# MCU.net
KiCad netlist of a schematic drawn in Altium Designer
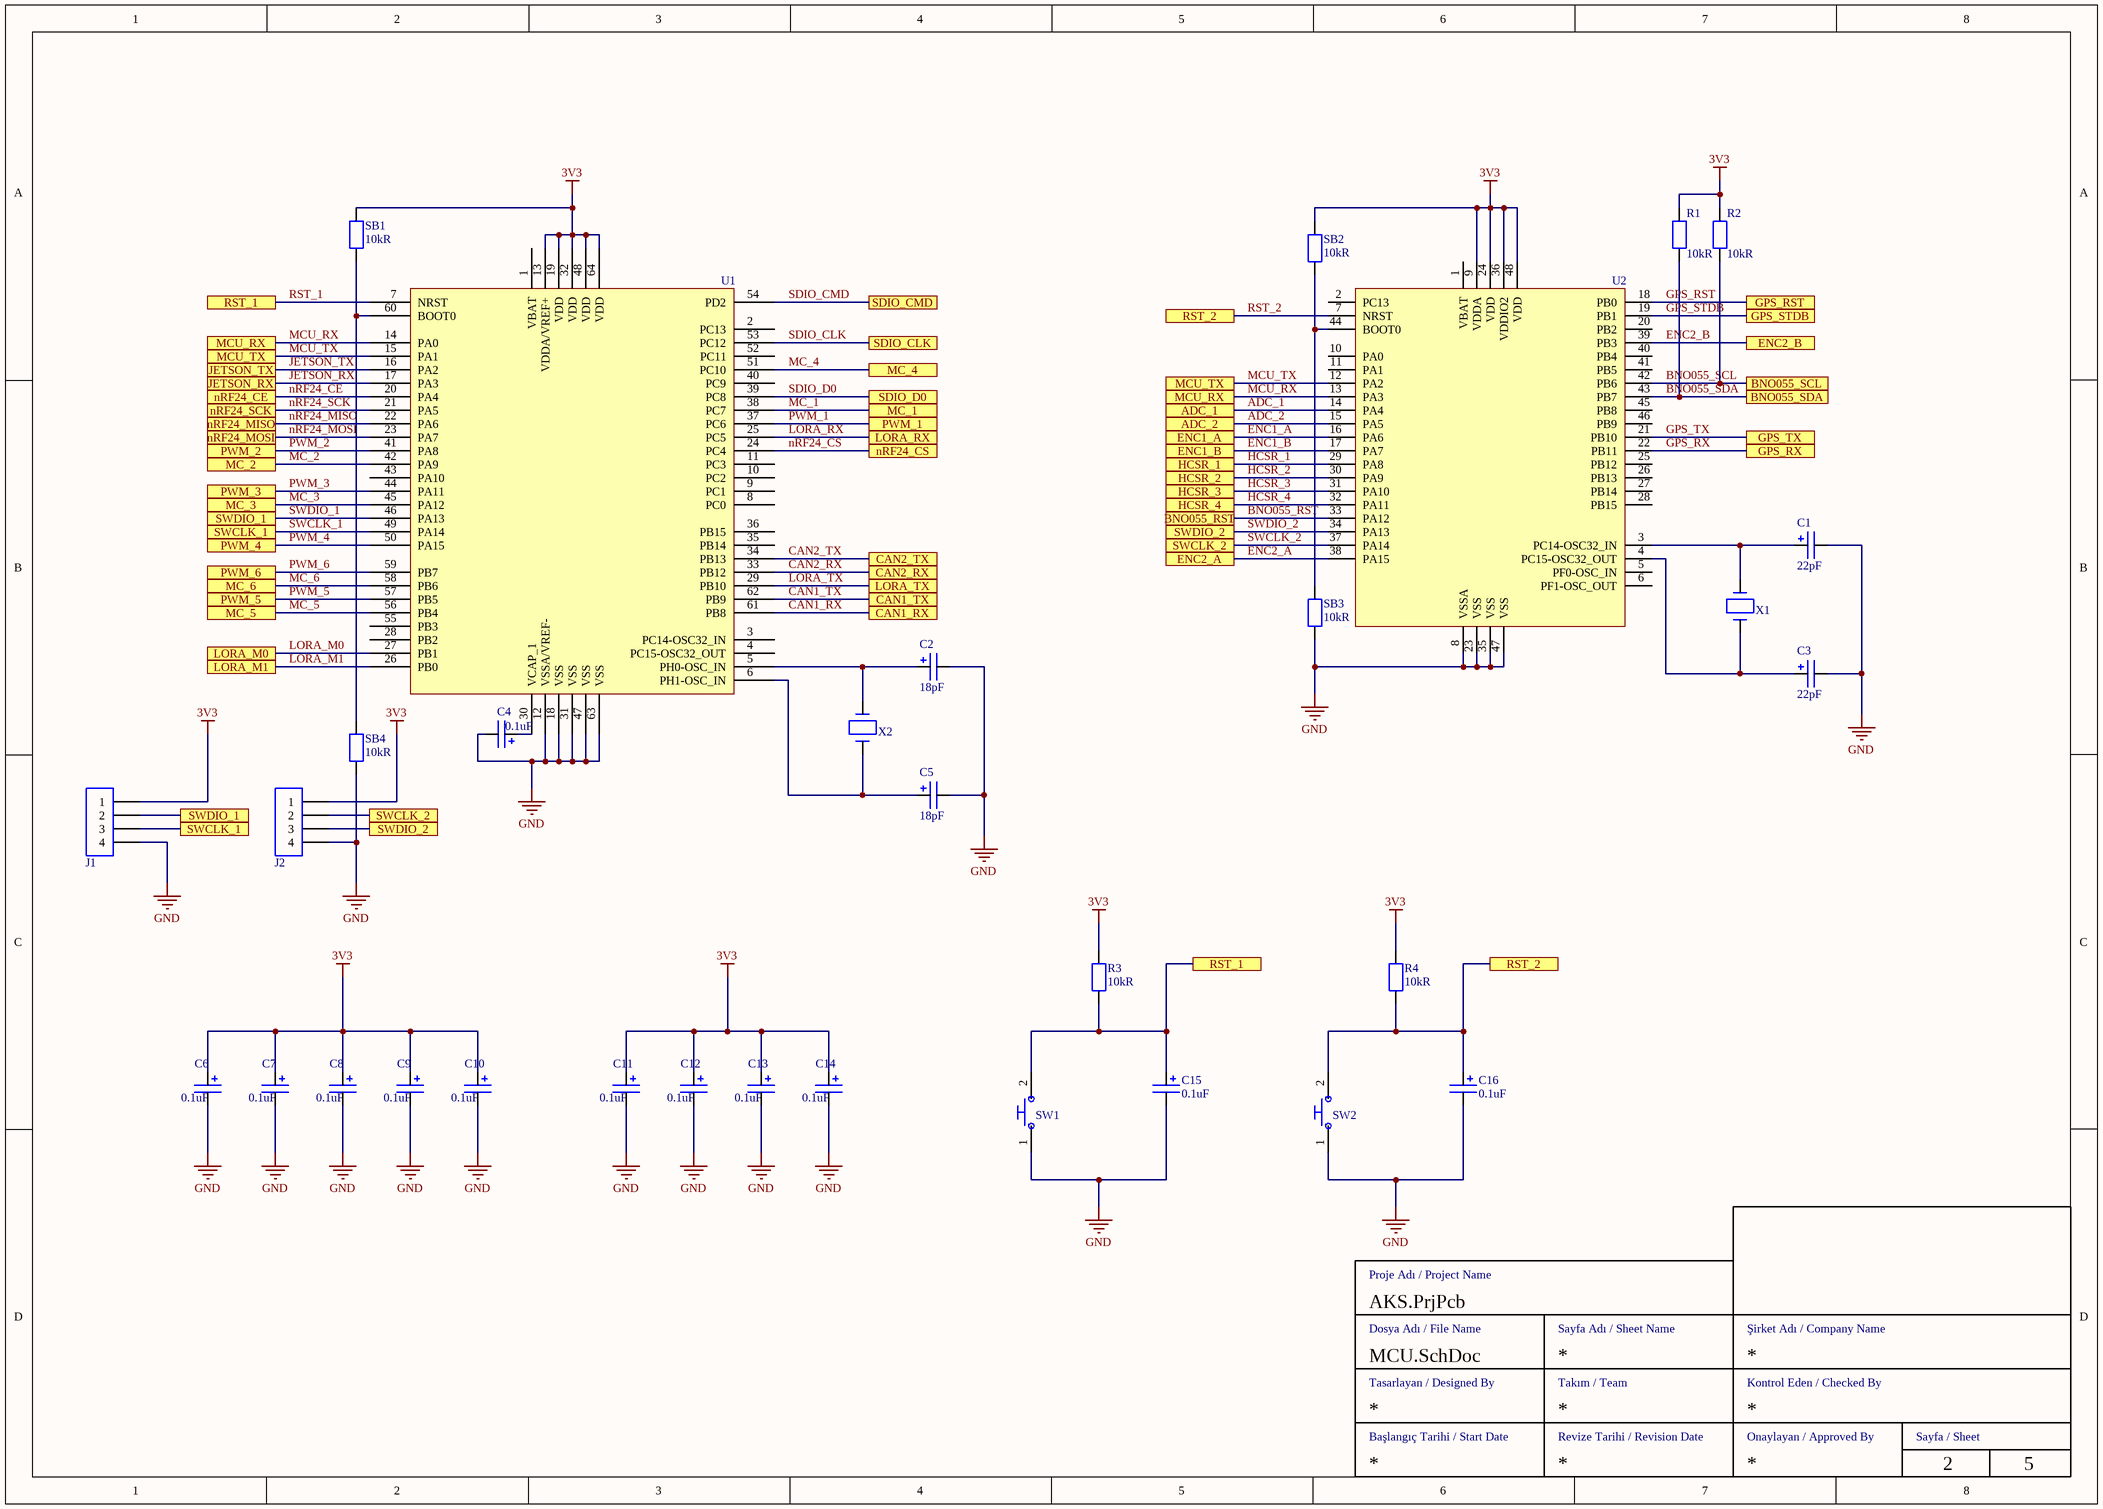
[diagram p0: MCU.SchDoc]

(export (version "E")
  (design (tool "Eeschema 10.0.6"))
  (components
    (comp (ref "C1")
      (value "22pF")
      (footprint "CAP 0603")
      (description "Multilayer Ceramic Capacitor")
      (fields (field (name "Comment") "CAP 0603"))
      (libsource (lib "Kaptanyums Lib") (part "CAP 0603"))
    )
    (comp (ref "C2")
      (value "18pF")
      (footprint "CAP 0603")
      (description "Multilayer Ceramic Capacitor")
      (fields (field (name "Comment") "CAP 0603"))
      (libsource (lib "Kaptanyums Lib") (part "CAP 0603"))
    )
    (comp (ref "C3")
      (value "22pF")
      (footprint "CAP 0603")
      (description "Multilayer Ceramic Capacitor")
      (fields (field (name "Comment") "CAP 0603"))
      (libsource (lib "Kaptanyums Lib") (part "CAP 0603"))
    )
    (comp (ref "C4")
      (value "0.1uF")
      (footprint "CAP 0603")
      (description "Multilayer Ceramic Capacitor")
      (fields (field (name "Comment") "CAP 0603"))
      (libsource (lib "Kaptanyums Lib") (part "CAP 0603"))
    )
    (comp (ref "C5")
      (value "18pF")
      (footprint "CAP 0603")
      (description "Multilayer Ceramic Capacitor")
      (fields (field (name "Comment") "CAP 0603"))
      (libsource (lib "Kaptanyums Lib") (part "CAP 0603"))
    )
    (comp (ref "C6")
      (value "0.1uF")
      (footprint "CAP 0603")
      (description "Multilayer Ceramic Capacitor")
      (fields (field (name "Comment") "CAP 0603"))
      (libsource (lib "Kaptanyums Lib") (part "CAP 0603"))
    )
    (comp (ref "C7")
      (value "0.1uF")
      (footprint "CAP 0603")
      (description "Multilayer Ceramic Capacitor")
      (fields (field (name "Comment") "CAP 0603"))
      (libsource (lib "Kaptanyums Lib") (part "CAP 0603"))
    )
    (comp (ref "C8")
      (value "0.1uF")
      (footprint "CAP 0603")
      (description "Multilayer Ceramic Capacitor")
      (fields (field (name "Comment") "CAP 0603"))
      (libsource (lib "Kaptanyums Lib") (part "CAP 0603"))
    )
    (comp (ref "C9")
      (value "0.1uF")
      (footprint "CAP 0603")
      (description "Multilayer Ceramic Capacitor")
      (fields (field (name "Comment") "CAP 0603"))
      (libsource (lib "Kaptanyums Lib") (part "CAP 0603"))
    )
    (comp (ref "C10")
      (value "0.1uF")
      (footprint "CAP 0603")
      (description "Multilayer Ceramic Capacitor")
      (fields (field (name "Comment") "CAP 0603"))
      (libsource (lib "Kaptanyums Lib") (part "CAP 0603"))
    )
    (comp (ref "C11")
      (value "0.1uF")
      (footprint "CAP 0603")
      (description "Multilayer Ceramic Capacitor")
      (fields (field (name "Comment") "CAP 0603"))
      (libsource (lib "Kaptanyums Lib") (part "CAP 0603"))
    )
    (comp (ref "C12")
      (value "0.1uF")
      (footprint "CAP 0603")
      (description "Multilayer Ceramic Capacitor")
      (fields (field (name "Comment") "CAP 0603"))
      (libsource (lib "Kaptanyums Lib") (part "CAP 0603"))
    )
    (comp (ref "C13")
      (value "0.1uF")
      (footprint "CAP 0603")
      (description "Multilayer Ceramic Capacitor")
      (fields (field (name "Comment") "CAP 0603"))
      (libsource (lib "Kaptanyums Lib") (part "CAP 0603"))
    )
    (comp (ref "C14")
      (value "0.1uF")
      (footprint "CAP 0603")
      (description "Multilayer Ceramic Capacitor")
      (fields (field (name "Comment") "CAP 0603"))
      (libsource (lib "Kaptanyums Lib") (part "CAP 0603"))
    )
    (comp (ref "C15")
      (value "0.1uF")
      (footprint "CAP 0603")
      (description "Multilayer Ceramic Capacitor")
      (fields (field (name "Comment") "CAP 0603"))
      (libsource (lib "Kaptanyums Lib") (part "CAP 0603"))
    )
    (comp (ref "C16")
      (value "0.1uF")
      (footprint "CAP 0603")
      (description "Multilayer Ceramic Capacitor")
      (fields (field (name "Comment") "CAP 0603"))
      (libsource (lib "Kaptanyums Lib") (part "CAP 0603"))
    )
    (comp (ref "J1")
      (value "146285-4")
      (footprint "HMATHT00C41")
      (description "Header for PCB")
      (libsource (lib "Kaptanyums Lib") (part "HMATHT00C41"))
    )
    (comp (ref "J2")
      (value "146285-4")
      (footprint "HMATHT00C41")
      (description "Header for PCB")
      (libsource (lib "Kaptanyums Lib") (part "HMATHT00C41"))
    )
    (comp (ref "R1")
      (value "10kR")
      (footprint "RESISTOR 0603")
      (description "SMD Chip Resistor")
      (fields (field (name "Comment") "RES 0603"))
      (libsource (lib "Kaptanyums Lib") (part "RES 0603"))
    )
    (comp (ref "R2")
      (value "10kR")
      (footprint "RESISTOR 0603")
      (description "SMD Chip Resistor")
      (fields (field (name "Comment") "RES 0603"))
      (libsource (lib "Kaptanyums Lib") (part "RES 0603"))
    )
    (comp (ref "R3")
      (value "10kR")
      (footprint "RESISTOR 0603")
      (description "SMD Chip Resistor")
      (fields (field (name "Comment") "RES 0603"))
      (libsource (lib "Kaptanyums Lib") (part "RES 0603"))
    )
    (comp (ref "R4")
      (value "10kR")
      (footprint "RESISTOR 0603")
      (description "SMD Chip Resistor")
      (fields (field (name "Comment") "RES 0603"))
      (libsource (lib "Kaptanyums Lib") (part "RES 0603"))
    )
    (comp (ref "SB1")
      (value "10kR")
      (footprint "RESISTOR 0603")
      (description "SMD Chip Resistor")
      (fields (field (name "Comment") "RES 0603"))
      (libsource (lib "Kaptanyums Lib") (part "RES 0603"))
    )
    (comp (ref "SB2")
      (value "10kR")
      (footprint "RESISTOR 0603")
      (description "SMD Chip Resistor")
      (fields (field (name "Comment") "RES 0603"))
      (libsource (lib "Kaptanyums Lib") (part "RES 0603"))
    )
    (comp (ref "SB3")
      (value "10kR")
      (footprint "RESISTOR 0603")
      (description "SMD Chip Resistor")
      (fields (field (name "Comment") "RES 0603"))
      (libsource (lib "Kaptanyums Lib") (part "RES 0603"))
    )
    (comp (ref "SB4")
      (value "10kR")
      (footprint "RESISTOR 0603")
      (description "SMD Chip Resistor")
      (fields (field (name "Comment") "RES 0603"))
      (libsource (lib "Kaptanyums Lib") (part "RES 0603"))
    )
    (comp (ref "SW1")
      (value "DS1042-03")
      (footprint "SWITCH-6X6")
      (description "Switch")
      (libsource (lib "Kaptanyums Lib") (part "DS1042-03"))
    )
    (comp (ref "SW2")
      (value "DS1042-03")
      (footprint "SWITCH-6X6")
      (description "Switch")
      (libsource (lib "Kaptanyums Lib") (part "DS1042-03"))
    )
    (comp (ref "U1")
      (value "STM32F446xC")
      (footprint "LQFP64")
      (description "STM32 ARM Cortex M4")
      (libsource (lib "Kaptanyums Lib") (part "STM32F446xC"))
    )
    (comp (ref "U2")
      (value "STM32F072C8")
      (footprint "LQFP48")
      (description "STM32 ARM Cortex M0")
      (libsource (lib "Kaptanyums Lib") (part "STM32F072C8"))
    )
    (comp (ref "X1")
      (value "RSM200S-32.768")
      (footprint "4-SOJ")
      (description "CRYSTAL")
      (libsource (lib "Kaptanyums Lib") (part "RSM200S-32.768"))
    )
    (comp (ref "X2")
      (value "ABM3-8.000")
      (footprint "2-SMD")
      (description "CRYSTAL")
      (libsource (lib "Kaptanyums Lib") (part "ABM3-8.000"))
    )
  )
  (nets
    (net (code "1") (name "/ADC_1") (class "Default")
      (node (ref "U2") (pin "14") (pinfunction "PA4_14") (pintype "passive"))
    )
    (net (code "2") (name "/ADC_2") (class "Default")
      (node (ref "U2") (pin "15") (pinfunction "PA5_15") (pintype "passive"))
    )
    (net (code "3") (name "/BNO055_RST") (class "Default")
      (node (ref "U2") (pin "33") (pinfunction "PA12_33") (pintype "passive"))
    )
    (net (code "4") (name "/BNO055_SCL") (class "Default")
      (node (ref "R2") (pin "1") (pinfunction "1_1") (pintype "passive"))
      (node (ref "U2") (pin "42") (pinfunction "PB6_42") (pintype "passive"))
    )
    (net (code "5") (name "/BNO055_SDA") (class "Default")
      (node (ref "R1") (pin "1") (pinfunction "1_1") (pintype "passive"))
      (node (ref "U2") (pin "43") (pinfunction "PB7_43") (pintype "passive"))
    )
    (net (code "6") (name "/CAN1_RX") (class "Default")
      (node (ref "U1") (pin "61") (pinfunction "PB8_61") (pintype "passive"))
    )
    (net (code "7") (name "/CAN1_TX") (class "Default")
      (node (ref "U1") (pin "62") (pinfunction "PB9_62") (pintype "passive"))
    )
    (net (code "8") (name "/CAN2_RX") (class "Default")
      (node (ref "U1") (pin "33") (pinfunction "PB12_33") (pintype "passive"))
    )
    (net (code "9") (name "/CAN2_TX") (class "Default")
      (node (ref "U1") (pin "34") (pinfunction "PB13_34") (pintype "passive"))
    )
    (net (code "10") (name "/ENC1_A") (class "Default")
      (node (ref "U2") (pin "16") (pinfunction "PA6_16") (pintype "passive"))
    )
    (net (code "11") (name "/ENC1_B") (class "Default")
      (node (ref "U2") (pin "17") (pinfunction "PA7_17") (pintype "passive"))
    )
    (net (code "12") (name "/ENC2_A") (class "Default")
      (node (ref "U2") (pin "38") (pinfunction "PA15_38") (pintype "passive"))
    )
    (net (code "13") (name "/ENC2_B") (class "Default")
      (node (ref "U2") (pin "39") (pinfunction "PB3_39") (pintype "passive"))
    )
    (net (code "14") (name "/GPS_RST") (class "Default")
      (node (ref "U2") (pin "18") (pinfunction "PB0_18") (pintype "passive"))
    )
    (net (code "15") (name "/GPS_RX") (class "Default")
      (node (ref "U2") (pin "22") (pinfunction "PB11_22") (pintype "passive"))
    )
    (net (code "16") (name "/GPS_STDB") (class "Default")
      (node (ref "U2") (pin "19") (pinfunction "PB1_19") (pintype "passive"))
    )
    (net (code "17") (name "/GPS_TX") (class "Default")
      (node (ref "U2") (pin "21") (pinfunction "PB10_21") (pintype "passive"))
    )
    (net (code "18") (name "/HCSR_1") (class "Default")
      (node (ref "U2") (pin "29") (pinfunction "PA8_29") (pintype "passive"))
    )
    (net (code "19") (name "/HCSR_2") (class "Default")
      (node (ref "U2") (pin "30") (pinfunction "PA9_30") (pintype "passive"))
    )
    (net (code "20") (name "/HCSR_3") (class "Default")
      (node (ref "U2") (pin "31") (pinfunction "PA10_31") (pintype "passive"))
    )
    (net (code "21") (name "/HCSR_4") (class "Default")
      (node (ref "U2") (pin "32") (pinfunction "PA11_32") (pintype "passive"))
    )
    (net (code "22") (name "/JETSON_RX") (class "Default")
      (node (ref "U1") (pin "17") (pinfunction "PA3_17") (pintype "passive"))
    )
    (net (code "23") (name "/JETSON_TX") (class "Default")
      (node (ref "U1") (pin "16") (pinfunction "PA2_16") (pintype "passive"))
    )
    (net (code "24") (name "/LORA_M0") (class "Default")
      (node (ref "U1") (pin "27") (pinfunction "PB1_27") (pintype "passive"))
    )
    (net (code "25") (name "/LORA_M1") (class "Default")
      (node (ref "U1") (pin "26") (pinfunction "PB0_26") (pintype "passive"))
    )
    (net (code "26") (name "/LORA_RX") (class "Default")
      (node (ref "U1") (pin "25") (pinfunction "PC5_25") (pintype "passive"))
    )
    (net (code "27") (name "/LORA_TX") (class "Default")
      (node (ref "U1") (pin "29") (pinfunction "PB10_29") (pintype "passive"))
    )
    (net (code "28") (name "/MCU_RX") (class "Default")
      (node (ref "U1") (pin "14") (pinfunction "PA0_14") (pintype "passive"))
      (node (ref "U2") (pin "13") (pinfunction "PA3_13") (pintype "passive"))
    )
    (net (code "29") (name "/MCU_TX") (class "Default")
      (node (ref "U1") (pin "15") (pinfunction "PA1_15") (pintype "passive"))
      (node (ref "U2") (pin "12") (pinfunction "PA2_12") (pintype "passive"))
    )
    (net (code "30") (name "/MC_1") (class "Default")
      (node (ref "U1") (pin "38") (pinfunction "PC7_38") (pintype "passive"))
    )
    (net (code "31") (name "/MC_2") (class "Default")
      (node (ref "U1") (pin "42") (pinfunction "PA9_42") (pintype "passive"))
    )
    (net (code "32") (name "/MC_3") (class "Default")
      (node (ref "U1") (pin "45") (pinfunction "PA12_45") (pintype "passive"))
    )
    (net (code "33") (name "/MC_4") (class "Default")
      (node (ref "U1") (pin "51") (pinfunction "PC10_51") (pintype "passive"))
    )
    (net (code "34") (name "/MC_5") (class "Default")
      (node (ref "U1") (pin "56") (pinfunction "PB4_56") (pintype "passive"))
    )
    (net (code "35") (name "/MC_6") (class "Default")
      (node (ref "U1") (pin "58") (pinfunction "PB6_58") (pintype "passive"))
    )
    (net (code "36") (name "/PWM_1") (class "Default")
      (node (ref "U1") (pin "37") (pinfunction "PC6_37") (pintype "passive"))
    )
    (net (code "37") (name "/PWM_2") (class "Default")
      (node (ref "U1") (pin "41") (pinfunction "PA8_41") (pintype "passive"))
    )
    (net (code "38") (name "/PWM_3") (class "Default")
      (node (ref "U1") (pin "44") (pinfunction "PA11_44") (pintype "passive"))
    )
    (net (code "39") (name "/PWM_4") (class "Default")
      (node (ref "U1") (pin "50") (pinfunction "PA15_50") (pintype "passive"))
    )
    (net (code "40") (name "/PWM_5") (class "Default")
      (node (ref "U1") (pin "57") (pinfunction "PB5_57") (pintype "passive"))
    )
    (net (code "41") (name "/PWM_6") (class "Default")
      (node (ref "U1") (pin "59") (pinfunction "PB7_59") (pintype "passive"))
    )
    (net (code "42") (name "/RST_1") (class "Default")
      (node (ref "C15") (pin "1") (pinfunction "1_1") (pintype "passive"))
      (node (ref "R3") (pin "1") (pinfunction "1_1") (pintype "passive"))
      (node (ref "SW1") (pin "2") (pinfunction "2_2") (pintype "passive"))
      (node (ref "U1") (pin "7") (pinfunction "NRST_7") (pintype "passive"))
    )
    (net (code "43") (name "/RST_2") (class "Default")
      (node (ref "C16") (pin "1") (pinfunction "1_1") (pintype "passive"))
      (node (ref "R4") (pin "1") (pinfunction "1_1") (pintype "passive"))
      (node (ref "SW2") (pin "2") (pinfunction "2_2") (pintype "passive"))
      (node (ref "U2") (pin "7") (pinfunction "NRST_7") (pintype "passive"))
    )
    (net (code "44") (name "/SDIO_CLK") (class "Default")
      (node (ref "U1") (pin "53") (pinfunction "PC12_53") (pintype "passive"))
    )
    (net (code "45") (name "/SDIO_CMD") (class "Default")
      (node (ref "U1") (pin "54") (pinfunction "PD2_54") (pintype "passive"))
    )
    (net (code "46") (name "/SDIO_D0") (class "Default")
      (node (ref "U1") (pin "39") (pinfunction "PC8_39") (pintype "passive"))
    )
    (net (code "47") (name "/SWCLK_1") (class "Default")
      (node (ref "J1") (pin "3") (pinfunction "3_3") (pintype "passive"))
      (node (ref "U1") (pin "49") (pinfunction "PA14_49") (pintype "passive"))
    )
    (net (code "48") (name "/SWCLK_2") (class "Default")
      (node (ref "J2") (pin "2") (pinfunction "2_2") (pintype "passive"))
      (node (ref "U2") (pin "37") (pinfunction "PA14_37") (pintype "passive"))
    )
    (net (code "49") (name "/SWDIO_1") (class "Default")
      (node (ref "J1") (pin "2") (pinfunction "2_2") (pintype "passive"))
      (node (ref "U1") (pin "46") (pinfunction "PA13_46") (pintype "passive"))
    )
    (net (code "50") (name "/SWDIO_2") (class "Default")
      (node (ref "J2") (pin "3") (pinfunction "3_3") (pintype "passive"))
      (node (ref "U2") (pin "34") (pinfunction "PA13_34") (pintype "passive"))
    )
    (net (code "51") (name "/nRF24_CE") (class "Default")
      (node (ref "U1") (pin "20") (pinfunction "PA4_20") (pintype "passive"))
    )
    (net (code "52") (name "/nRF24_CS") (class "Default")
      (node (ref "U1") (pin "24") (pinfunction "PC4_24") (pintype "passive"))
    )
    (net (code "53") (name "/nRF24_MISO") (class "Default")
      (node (ref "U1") (pin "22") (pinfunction "PA6_22") (pintype "passive"))
    )
    (net (code "54") (name "/nRF24_MOSI") (class "Default")
      (node (ref "U1") (pin "23") (pinfunction "PA7_23") (pintype "passive"))
    )
    (net (code "55") (name "/nRF24_SCK") (class "Default")
      (node (ref "U1") (pin "21") (pinfunction "PA5_21") (pintype "passive"))
    )
    (net (code "56") (name "3V3") (class "Default")
      (node (ref "C10") (pin "1") (pinfunction "1_1") (pintype "passive"))
      (node (ref "C11") (pin "1") (pinfunction "1_1") (pintype "passive"))
      (node (ref "C12") (pin "1") (pinfunction "1_1") (pintype "passive"))
      (node (ref "C13") (pin "1") (pinfunction "1_1") (pintype "passive"))
      (node (ref "C14") (pin "1") (pinfunction "1_1") (pintype "passive"))
      (node (ref "C6") (pin "1") (pinfunction "1_1") (pintype "passive"))
      (node (ref "C7") (pin "1") (pinfunction "1_1") (pintype "passive"))
      (node (ref "C8") (pin "1") (pinfunction "1_1") (pintype "passive"))
      (node (ref "C9") (pin "1") (pinfunction "1_1") (pintype "passive"))
      (node (ref "J1") (pin "1") (pinfunction "1_1") (pintype "passive"))
      (node (ref "J2") (pin "1") (pinfunction "1_1") (pintype "passive"))
      (node (ref "R1") (pin "2") (pinfunction "2_2") (pintype "passive"))
      (node (ref "R2") (pin "2") (pinfunction "2_2") (pintype "passive"))
      (node (ref "R3") (pin "2") (pinfunction "2_2") (pintype "passive"))
      (node (ref "R4") (pin "2") (pinfunction "2_2") (pintype "passive"))
      (node (ref "SB1") (pin "2") (pinfunction "2_2") (pintype "passive"))
      (node (ref "SB2") (pin "2") (pinfunction "2_2") (pintype "passive"))
      (node (ref "U1") (pin "13") (pinfunction "VDDA/VREF+_13") (pintype "passive"))
      (node (ref "U1") (pin "19") (pinfunction "VDD_19") (pintype "passive"))
      (node (ref "U1") (pin "32") (pinfunction "VDD_32") (pintype "passive"))
      (node (ref "U1") (pin "48") (pinfunction "VDD_48") (pintype "passive"))
      (node (ref "U1") (pin "64") (pinfunction "VDD_64") (pintype "passive"))
      (node (ref "U2") (pin "24") (pinfunction "VDD_24") (pintype "passive"))
      (node (ref "U2") (pin "36") (pinfunction "VDDIO2_36") (pintype "passive"))
      (node (ref "U2") (pin "48") (pinfunction "VDD_48") (pintype "passive"))
      (node (ref "U2") (pin "9") (pinfunction "VDDA_9") (pintype "passive"))
    )
    (net (code "57") (name "GND") (class "Default")
      (node (ref "C1") (pin "2") (pinfunction "2_2") (pintype "passive"))
      (node (ref "C10") (pin "2") (pinfunction "2_2") (pintype "passive"))
      (node (ref "C11") (pin "2") (pinfunction "2_2") (pintype "passive"))
      (node (ref "C12") (pin "2") (pinfunction "2_2") (pintype "passive"))
      (node (ref "C13") (pin "2") (pinfunction "2_2") (pintype "passive"))
      (node (ref "C14") (pin "2") (pinfunction "2_2") (pintype "passive"))
      (node (ref "C15") (pin "2") (pinfunction "2_2") (pintype "passive"))
      (node (ref "C16") (pin "2") (pinfunction "2_2") (pintype "passive"))
      (node (ref "C2") (pin "2") (pinfunction "2_2") (pintype "passive"))
      (node (ref "C3") (pin "2") (pinfunction "2_2") (pintype "passive"))
      (node (ref "C4") (pin "2") (pinfunction "2_2") (pintype "passive"))
      (node (ref "C5") (pin "2") (pinfunction "2_2") (pintype "passive"))
      (node (ref "C6") (pin "2") (pinfunction "2_2") (pintype "passive"))
      (node (ref "C7") (pin "2") (pinfunction "2_2") (pintype "passive"))
      (node (ref "C8") (pin "2") (pinfunction "2_2") (pintype "passive"))
      (node (ref "C9") (pin "2") (pinfunction "2_2") (pintype "passive"))
      (node (ref "J1") (pin "4") (pinfunction "4_4") (pintype "passive"))
      (node (ref "J2") (pin "4") (pinfunction "4_4") (pintype "passive"))
      (node (ref "SB3") (pin "1") (pinfunction "1_1") (pintype "passive"))
      (node (ref "SB4") (pin "1") (pinfunction "1_1") (pintype "passive"))
      (node (ref "SW1") (pin "1") (pinfunction "1_1") (pintype "passive"))
      (node (ref "SW2") (pin "1") (pinfunction "1_1") (pintype "passive"))
      (node (ref "U1") (pin "12") (pinfunction "VSSA/VREF-_12") (pintype "passive"))
      (node (ref "U1") (pin "18") (pinfunction "VSS_18") (pintype "passive"))
      (node (ref "U1") (pin "31") (pinfunction "VSS_31") (pintype "passive"))
      (node (ref "U1") (pin "47") (pinfunction "VSS_47") (pintype "passive"))
      (node (ref "U1") (pin "63") (pinfunction "VSS_63") (pintype "passive"))
      (node (ref "U2") (pin "23") (pinfunction "VSS_23") (pintype "passive"))
      (node (ref "U2") (pin "35") (pinfunction "VSS_35") (pintype "passive"))
      (node (ref "U2") (pin "47") (pinfunction "VSS_47") (pintype "passive"))
      (node (ref "U2") (pin "8") (pinfunction "VSSA_8") (pintype "passive"))
    )
    (net (code "58") (name "Net-(U1-BOOT0)") (class "Default")
      (node (ref "SB1") (pin "1") (pinfunction "1_1") (pintype "passive"))
      (node (ref "SB4") (pin "2") (pinfunction "2_2") (pintype "passive"))
      (node (ref "U1") (pin "60") (pinfunction "BOOT0_60") (pintype "passive"))
    )
    (net (code "59") (name "Net-(U1-PH0-OSC_IN)") (class "Default")
      (node (ref "C2") (pin "1") (pinfunction "1_1") (pintype "passive"))
      (node (ref "U1") (pin "5") (pinfunction "PH0-OSC_IN_5") (pintype "passive"))
      (node (ref "X2") (pin "1") (pinfunction "1_1") (pintype "passive"))
    )
    (net (code "60") (name "Net-(U1-PH1-OSC_IN)") (class "Default")
      (node (ref "C5") (pin "1") (pinfunction "1_1") (pintype "passive"))
      (node (ref "U1") (pin "6") (pinfunction "PH1-OSC_IN_6") (pintype "passive"))
      (node (ref "X2") (pin "2") (pinfunction "2_2") (pintype "passive"))
    )
    (net (code "61") (name "Net-(U1-VCAP_1)") (class "Default")
      (node (ref "C4") (pin "1") (pinfunction "1_1") (pintype "passive"))
      (node (ref "U1") (pin "30") (pinfunction "VCAP_1_30") (pintype "passive"))
    )
    (net (code "62") (name "Net-(U2-BOOT0)") (class "Default")
      (node (ref "SB2") (pin "1") (pinfunction "1_1") (pintype "passive"))
      (node (ref "SB3") (pin "2") (pinfunction "2_2") (pintype "passive"))
      (node (ref "U2") (pin "44") (pinfunction "BOOT0_44") (pintype "passive"))
    )
    (net (code "63") (name "Net-(U2-PC14-OSC32_IN)") (class "Default")
      (node (ref "C1") (pin "1") (pinfunction "1_1") (pintype "passive"))
      (node (ref "U2") (pin "3") (pinfunction "PC14-OSC32_IN_3") (pintype "passive"))
      (node (ref "X1") (pin "1") (pinfunction "1_1") (pintype "passive"))
    )
    (net (code "64") (name "Net-(U2-PC15-OSC32_OUT)") (class "Default")
      (node (ref "C3") (pin "1") (pinfunction "1_1") (pintype "passive"))
      (node (ref "U2") (pin "4") (pinfunction "PC15-OSC32_OUT_4") (pintype "passive"))
      (node (ref "X1") (pin "4") (pinfunction "4_4") (pintype "passive"))
    )
    (net (code "65") (name "unconnected-(U1-PA10-Pad43)") (class "Default")
      (node (ref "U1") (pin "43") (pinfunction "PA10_43") (pintype "passive"))
    )
    (net (code "66") (name "unconnected-(U1-PB2-Pad28)") (class "Default")
      (node (ref "U1") (pin "28") (pinfunction "PB2_28") (pintype "passive"))
    )
    (net (code "67") (name "unconnected-(U1-PB3-Pad55)") (class "Default")
      (node (ref "U1") (pin "55") (pinfunction "PB3_55") (pintype "passive"))
    )
    (net (code "68") (name "unconnected-(U1-PB14-Pad35)") (class "Default")
      (node (ref "U1") (pin "35") (pinfunction "PB14_35") (pintype "passive"))
    )
    (net (code "69") (name "unconnected-(U1-PB15-Pad36)") (class "Default")
      (node (ref "U1") (pin "36") (pinfunction "PB15_36") (pintype "passive"))
    )
    (net (code "70") (name "unconnected-(U1-PC0-Pad8)") (class "Default")
      (node (ref "U1") (pin "8") (pinfunction "PC0_8") (pintype "passive"))
    )
    (net (code "71") (name "unconnected-(U1-PC1-Pad9)") (class "Default")
      (node (ref "U1") (pin "9") (pinfunction "PC1_9") (pintype "passive"))
    )
    (net (code "72") (name "unconnected-(U1-PC2-Pad10)") (class "Default")
      (node (ref "U1") (pin "10") (pinfunction "PC2_10") (pintype "passive"))
    )
    (net (code "73") (name "unconnected-(U1-PC3-Pad11)") (class "Default")
      (node (ref "U1") (pin "11") (pinfunction "PC3_11") (pintype "passive"))
    )
    (net (code "74") (name "unconnected-(U1-PC9-Pad40)") (class "Default")
      (node (ref "U1") (pin "40") (pinfunction "PC9_40") (pintype "passive"))
    )
    (net (code "75") (name "unconnected-(U1-PC11-Pad52)") (class "Default")
      (node (ref "U1") (pin "52") (pinfunction "PC11_52") (pintype "passive"))
    )
    (net (code "76") (name "unconnected-(U1-PC13-Pad2)") (class "Default")
      (node (ref "U1") (pin "2") (pinfunction "PC13_2") (pintype "passive"))
    )
    (net (code "77") (name "unconnected-(U1-PC14-OSC32_IN-Pad3)") (class "Default")
      (node (ref "U1") (pin "3") (pinfunction "PC14-OSC32_IN_3") (pintype "passive"))
    )
    (net (code "78") (name "unconnected-(U1-PC15-OSC32_OUT-Pad4)") (class "Default")
      (node (ref "U1") (pin "4") (pinfunction "PC15-OSC32_OUT_4") (pintype "passive"))
    )
    (net (code "79") (name "unconnected-(U1-VBAT-Pad1)") (class "Default")
      (node (ref "U1") (pin "1") (pinfunction "VBAT_1") (pintype "passive"))
    )
    (net (code "80") (name "unconnected-(U2-PA0-Pad10)") (class "Default")
      (node (ref "U2") (pin "10") (pinfunction "PA0_10") (pintype "passive"))
    )
    (net (code "81") (name "unconnected-(U2-PA1-Pad11)") (class "Default")
      (node (ref "U2") (pin "11") (pinfunction "PA1_11") (pintype "passive"))
    )
    (net (code "82") (name "unconnected-(U2-PB2-Pad20)") (class "Default")
      (node (ref "U2") (pin "20") (pinfunction "PB2_20") (pintype "passive"))
    )
    (net (code "83") (name "unconnected-(U2-PB4-Pad40)") (class "Default")
      (node (ref "U2") (pin "40") (pinfunction "PB4_40") (pintype "passive"))
    )
    (net (code "84") (name "unconnected-(U2-PB5-Pad41)") (class "Default")
      (node (ref "U2") (pin "41") (pinfunction "PB5_41") (pintype "passive"))
    )
    (net (code "85") (name "unconnected-(U2-PB8-Pad45)") (class "Default")
      (node (ref "U2") (pin "45") (pinfunction "PB8_45") (pintype "passive"))
    )
    (net (code "86") (name "unconnected-(U2-PB9-Pad46)") (class "Default")
      (node (ref "U2") (pin "46") (pinfunction "PB9_46") (pintype "passive"))
    )
    (net (code "87") (name "unconnected-(U2-PB12-Pad25)") (class "Default")
      (node (ref "U2") (pin "25") (pinfunction "PB12_25") (pintype "passive"))
    )
    (net (code "88") (name "unconnected-(U2-PB13-Pad26)") (class "Default")
      (node (ref "U2") (pin "26") (pinfunction "PB13_26") (pintype "passive"))
    )
    (net (code "89") (name "unconnected-(U2-PB14-Pad27)") (class "Default")
      (node (ref "U2") (pin "27") (pinfunction "PB14_27") (pintype "passive"))
    )
    (net (code "90") (name "unconnected-(U2-PB15-Pad28)") (class "Default")
      (node (ref "U2") (pin "28") (pinfunction "PB15_28") (pintype "passive"))
    )
    (net (code "91") (name "unconnected-(U2-PC13-Pad2)") (class "Default")
      (node (ref "U2") (pin "2") (pinfunction "PC13_2") (pintype "passive"))
    )
    (net (code "92") (name "unconnected-(U2-PF0-OSC_IN-Pad5)") (class "Default")
      (node (ref "U2") (pin "5") (pinfunction "PF0-OSC_IN_5") (pintype "passive"))
    )
    (net (code "93") (name "unconnected-(U2-PF1-OSC_OUT-Pad6)") (class "Default")
      (node (ref "U2") (pin "6") (pinfunction "PF1-OSC_OUT_6") (pintype "passive"))
    )
    (net (code "94") (name "unconnected-(U2-VBAT-Pad1)") (class "Default")
      (node (ref "U2") (pin "1") (pinfunction "VBAT_1") (pintype "passive"))
    )
  )
)
